# motorboard_v1_2.net
KiCad netlist of a schematic drawn in EAGLE
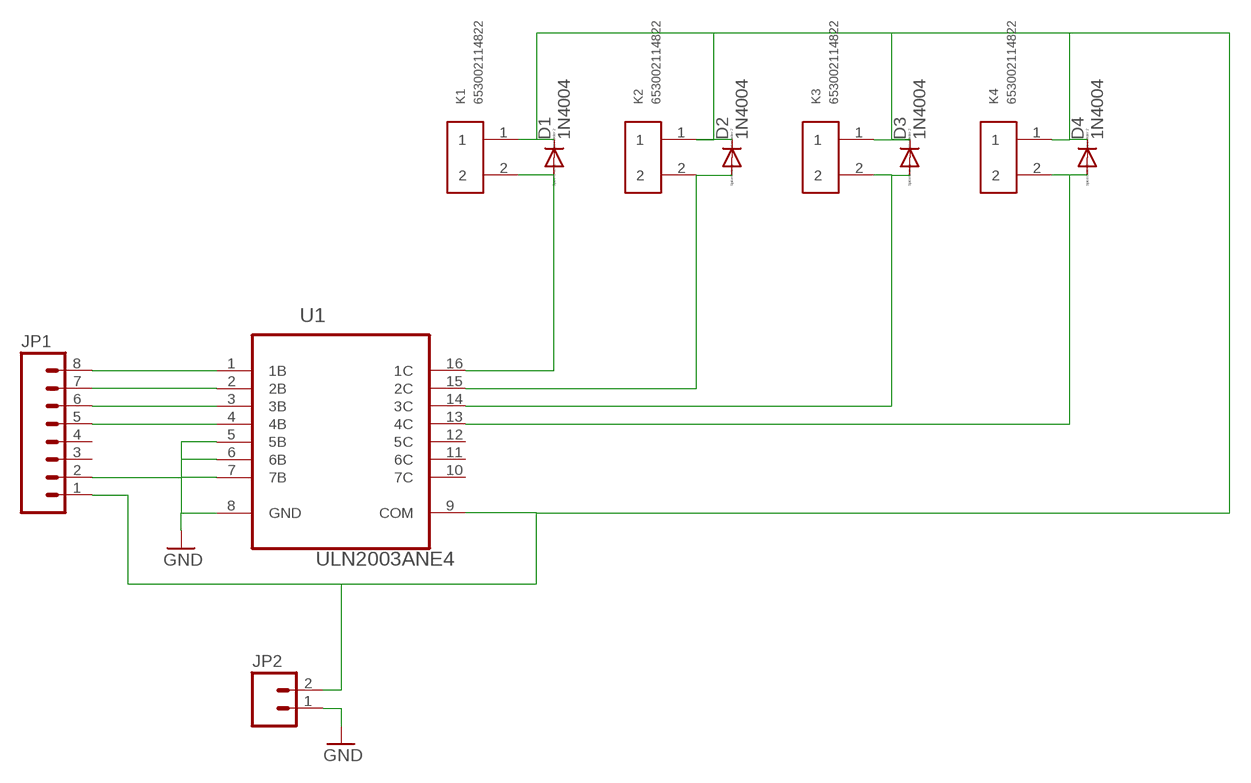
[diagram p0: schematic, sheet 1]

(export (version "E")
  (design (tool "Eeschema 10.0.6"))
  (components
    (comp (ref "D1")
      (value "1N4004")
      (footprint "eagle-import:DO41-10")
      (fields (field (name "MF") "NTE ELECTRONICS"))
      (libsource (lib "eagle-import") (part "1N4004"))
    )
    (comp (ref "D2")
      (value "1N4004")
      (footprint "eagle-import:DO41-10")
      (fields (field (name "MF") "NTE ELECTRONICS"))
      (libsource (lib "eagle-import") (part "1N4004"))
    )
    (comp (ref "D3")
      (value "1N4004")
      (footprint "eagle-import:DO41-10")
      (fields (field (name "MF") "NTE ELECTRONICS"))
      (libsource (lib "eagle-import") (part "1N4004"))
    )
    (comp (ref "D4")
      (value "1N4004")
      (footprint "eagle-import:DO41-10")
      (fields (field (name "MF") "NTE ELECTRONICS"))
      (libsource (lib "eagle-import") (part "1N4004"))
    )
    (comp (ref "JP1")
      (value "M08NO_SILK_FEMALE_PTH")
      (footprint "eagle-import:1X08_NO_SILK")
      (libsource (lib "eagle-import") (part "M08NO_SILK_FEMALE_PTH"))
    )
    (comp (ref "JP2")
      (value "M02LOCK_LONGPADS")
      (footprint "eagle-import:1X02_LOCK_LONGPADS")
      (libsource (lib "eagle-import") (part "M02LOCK_LONGPADS"))
    )
    (comp (ref "K1")
      (value "653002114822")
      (footprint "eagle-import:653002114822")
      (libsource (lib "eagle-import") (part "653002114822"))
    )
    (comp (ref "K2")
      (value "653002114822")
      (footprint "eagle-import:653002114822")
      (libsource (lib "eagle-import") (part "653002114822"))
    )
    (comp (ref "K3")
      (value "653002114822")
      (footprint "eagle-import:653002114822")
      (libsource (lib "eagle-import") (part "653002114822"))
    )
    (comp (ref "K4")
      (value "653002114822")
      (footprint "eagle-import:653002114822")
      (libsource (lib "eagle-import") (part "653002114822"))
    )
    (comp (ref "U1")
      (value "ULN2003ANE4")
      (footprint "eagle-import:DIP254P762X508-16")
      (libsource (lib "eagle-import") (part "ULN2003ANE4"))
    )
  )
  (nets
    (net (code "1") (name "GND") (class "Default")
      (node (ref "JP1") (pin "2") (pinfunction "2_2") (pintype "passive"))
      (node (ref "JP2") (pin "1") (pinfunction "1_1") (pintype "passive"))
      (node (ref "U1") (pin "5") (pinfunction "5B_5") (pintype "input"))
      (node (ref "U1") (pin "6") (pinfunction "6B_6") (pintype "input"))
      (node (ref "U1") (pin "7") (pinfunction "7B_7") (pintype "input"))
      (node (ref "U1") (pin "8") (pinfunction "GND_8") (pintype "passive"))
    )
    (net (code "2") (name "Net-(U1-1B)") (class "Default")
      (node (ref "JP1") (pin "8") (pinfunction "8_8") (pintype "passive"))
      (node (ref "U1") (pin "1") (pinfunction "1B_1") (pintype "input"))
    )
    (net (code "3") (name "Net-(U1-1C)") (class "Default")
      (node (ref "D1") (pin "A") (pinfunction "A_A") (pintype "passive"))
      (node (ref "K1") (pin "2") (pinfunction "2_2") (pintype "bidirectional"))
      (node (ref "U1") (pin "16") (pinfunction "1C_16") (pintype "output"))
    )
    (net (code "4") (name "Net-(U1-2B)") (class "Default")
      (node (ref "JP1") (pin "7") (pinfunction "7_7") (pintype "passive"))
      (node (ref "U1") (pin "2") (pinfunction "2B_2") (pintype "input"))
    )
    (net (code "5") (name "Net-(U1-2C)") (class "Default")
      (node (ref "D2") (pin "A") (pinfunction "A_A") (pintype "passive"))
      (node (ref "K2") (pin "2") (pinfunction "2_2") (pintype "bidirectional"))
      (node (ref "U1") (pin "15") (pinfunction "2C_15") (pintype "output"))
    )
    (net (code "6") (name "Net-(U1-3B)") (class "Default")
      (node (ref "JP1") (pin "6") (pinfunction "6_6") (pintype "passive"))
      (node (ref "U1") (pin "3") (pinfunction "3B_3") (pintype "input"))
    )
    (net (code "7") (name "Net-(U1-3C)") (class "Default")
      (node (ref "D3") (pin "A") (pinfunction "A_A") (pintype "passive"))
      (node (ref "K3") (pin "2") (pinfunction "2_2") (pintype "bidirectional"))
      (node (ref "U1") (pin "14") (pinfunction "3C_14") (pintype "output"))
    )
    (net (code "8") (name "Net-(U1-4B)") (class "Default")
      (node (ref "JP1") (pin "5") (pinfunction "5_5") (pintype "passive"))
      (node (ref "U1") (pin "4") (pinfunction "4B_4") (pintype "input"))
    )
    (net (code "9") (name "Net-(U1-4C)") (class "Default")
      (node (ref "D4") (pin "A") (pinfunction "A_A") (pintype "passive"))
      (node (ref "K4") (pin "2") (pinfunction "2_2") (pintype "bidirectional"))
      (node (ref "U1") (pin "13") (pinfunction "4C_13") (pintype "output"))
    )
    (net (code "10") (name "Net-(U1-COM)") (class "Default")
      (node (ref "D1") (pin "C") (pinfunction "C_C") (pintype "passive"))
      (node (ref "D2") (pin "C") (pinfunction "C_C") (pintype "passive"))
      (node (ref "D3") (pin "C") (pinfunction "C_C") (pintype "passive"))
      (node (ref "D4") (pin "C") (pinfunction "C_C") (pintype "passive"))
      (node (ref "JP1") (pin "1") (pinfunction "1_1") (pintype "passive"))
      (node (ref "JP2") (pin "2") (pinfunction "2_2") (pintype "passive"))
      (node (ref "K1") (pin "1") (pinfunction "1_1") (pintype "bidirectional"))
      (node (ref "K2") (pin "1") (pinfunction "1_1") (pintype "bidirectional"))
      (node (ref "K3") (pin "1") (pinfunction "1_1") (pintype "bidirectional"))
      (node (ref "K4") (pin "1") (pinfunction "1_1") (pintype "bidirectional"))
      (node (ref "U1") (pin "9") (pinfunction "COM_9") (pintype "output"))
    )
    (net (code "11") (name "unconnected-(JP1-Pad3)") (class "Default")
      (node (ref "JP1") (pin "3") (pinfunction "3_3") (pintype "passive"))
    )
    (net (code "12") (name "unconnected-(JP1-Pad4)") (class "Default")
      (node (ref "JP1") (pin "4") (pinfunction "4_4") (pintype "passive"))
    )
    (net (code "13") (name "unconnected-(U1-5C-Pad12)") (class "Default")
      (node (ref "U1") (pin "12") (pinfunction "5C_12") (pintype "output"))
    )
    (net (code "14") (name "unconnected-(U1-6C-Pad11)") (class "Default")
      (node (ref "U1") (pin "11") (pinfunction "6C_11") (pintype "output"))
    )
    (net (code "15") (name "unconnected-(U1-7C-Pad10)") (class "Default")
      (node (ref "U1") (pin "10") (pinfunction "7C_10") (pintype "output"))
    )
  )
)
